# counter-defender-esp8266-pir-mk-1_0.net
KiCad netlist of a schematic drawn in EAGLE
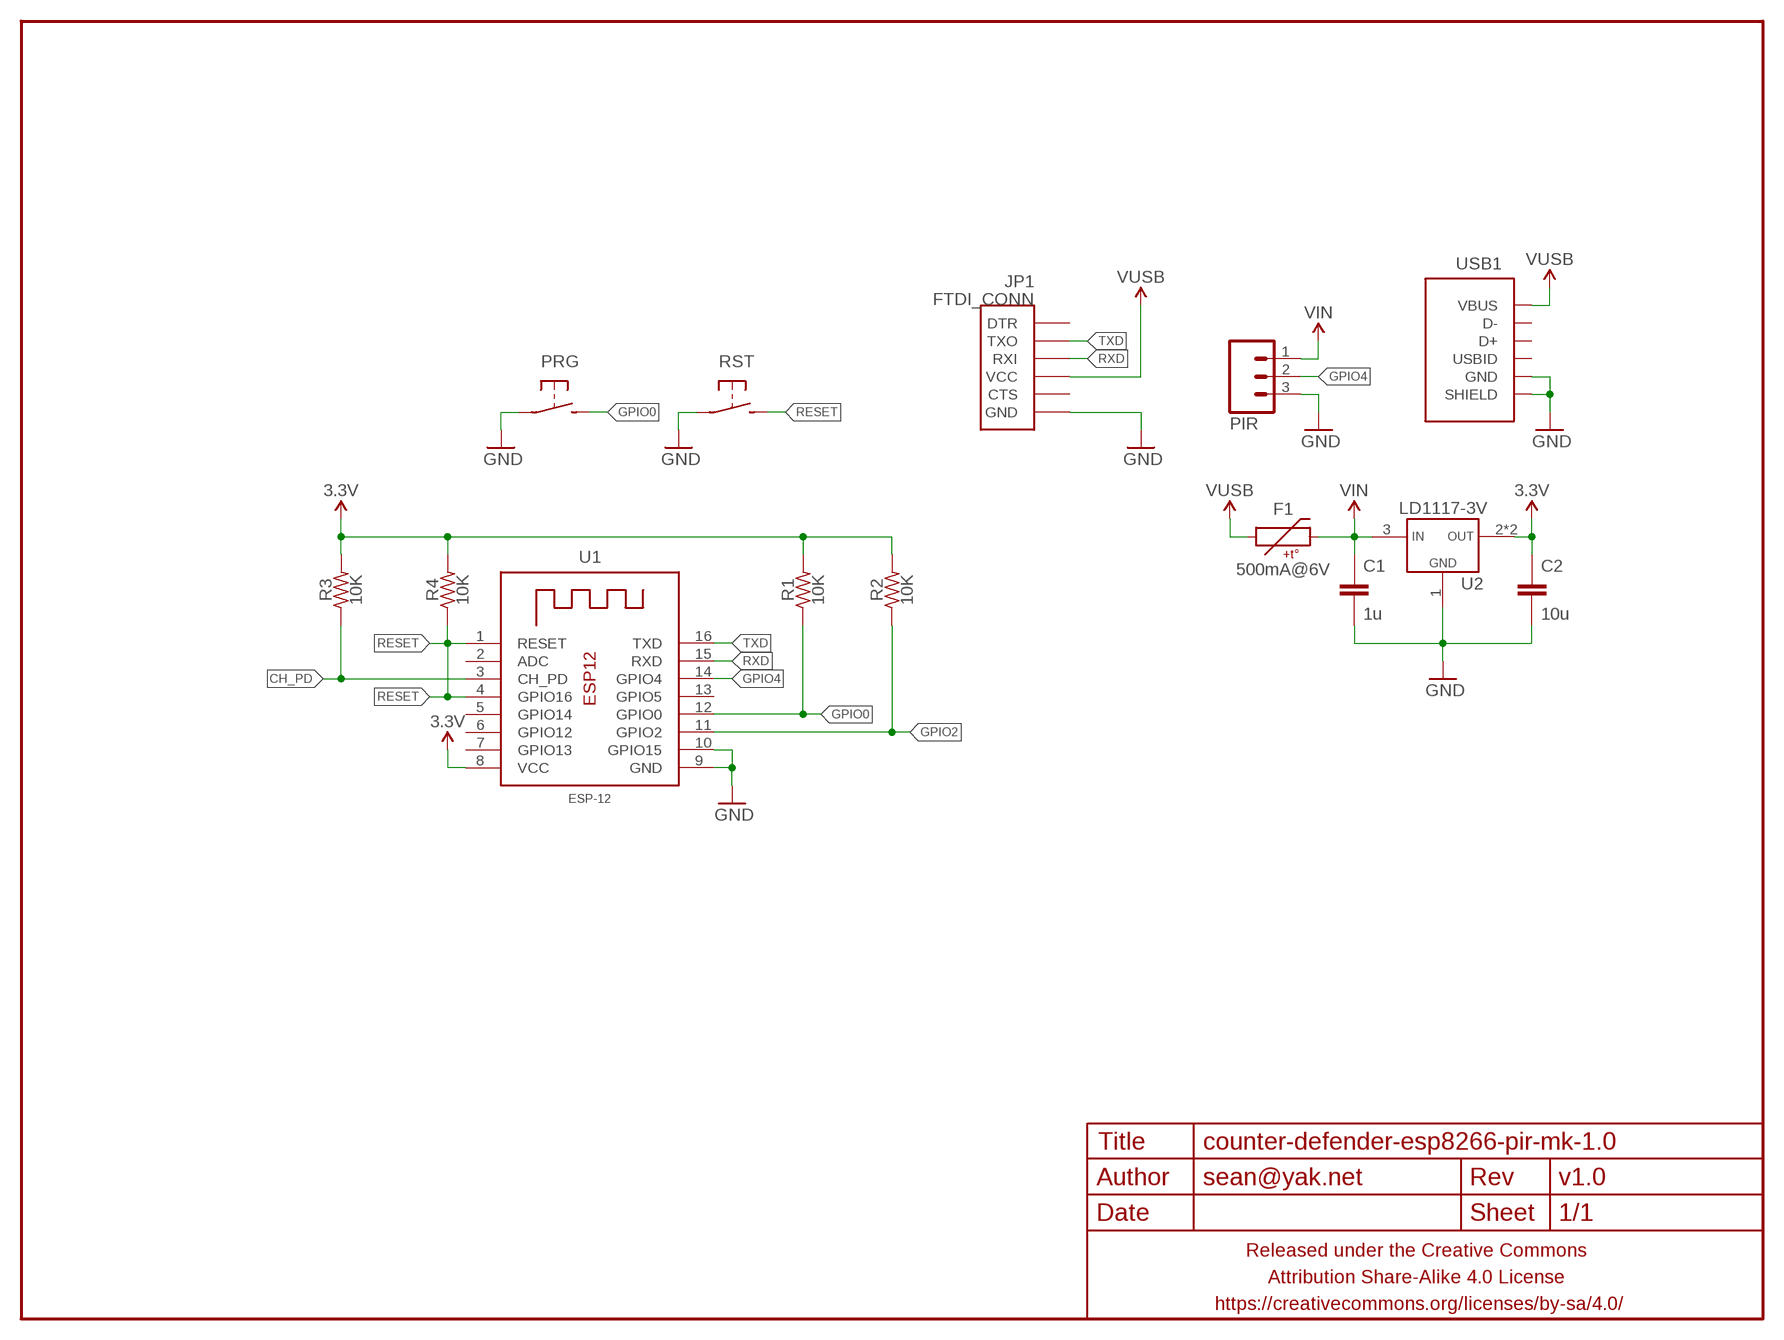
[diagram p0: schematic, sheet 1]

(export (version "E")
  (design (tool "Eeschema 10.0.6"))
  (components
    (comp (ref "C1")
      (value "1u")
      (footprint "eagle-import:C0805-TIGHTER")
      (libsource (lib "eagle-import") (part "CAPACITOR-CERAMICC0805-TIGHTER"))
    )
    (comp (ref "C2")
      (value "10u")
      (footprint "eagle-import:C0805-TIGHTER")
      (libsource (lib "eagle-import") (part "CAPACITOR-CERAMICC0805-TIGHTER"))
    )
    (comp (ref "F1")
      (value "500mA@6V")
      (footprint "eagle-import:PTC0805")
      (libsource (lib "eagle-import") (part "PTC0805"))
    )
    (comp (ref "FRAME1")
      (value "FRAME-LETTERNO_PACKAGE")
      (footprint "eagle-import:DUMMY")
      (fields (field (name "DESIGNER") "sean@yak.net") (field (name "VERSION") "v1.0"))
      (libsource (lib "eagle-import") (part "FRAME-LETTERNO_PACKAGE"))
    )
    (comp (ref "JP1")
      (value "FTDI_CONN")
      (footprint "eagle-import:FTDI_CONN")
      (libsource (lib "eagle-import") (part "FTDI_CONN"))
    )
    (comp (ref "PIR")
      (value "M03PTH-CENTERED")
      (footprint "eagle-import:1X03-CENTERED")
      (libsource (lib "eagle-import") (part "M03PTH-CENTERED"))
    )
    (comp (ref "PRG")
      (value "SPST-NO-TACTSMD-TINIER")
      (footprint "eagle-import:TACTILE_SWITCH_SMD_TINY")
      (libsource (lib "eagle-import") (part "SPST-NO-TACTSMD-TINIER"))
    )
    (comp (ref "R1")
      (value "10K")
      (footprint "eagle-import:R0603-TIGHTER")
      (libsource (lib "eagle-import") (part "RESISTORR0603-TIGHTER"))
    )
    (comp (ref "R2")
      (value "10K")
      (footprint "eagle-import:R0603-TIGHTER")
      (libsource (lib "eagle-import") (part "RESISTORR0603-TIGHTER"))
    )
    (comp (ref "R3")
      (value "10K")
      (footprint "eagle-import:R0603-TIGHTER")
      (libsource (lib "eagle-import") (part "RESISTORR0603-TIGHTER"))
    )
    (comp (ref "R4")
      (value "10K")
      (footprint "eagle-import:R0603-TIGHTER")
      (libsource (lib "eagle-import") (part "RESISTORR0603-TIGHTER"))
    )
    (comp (ref "RST")
      (value "SPST-NO-TACTSMD-TINIER")
      (footprint "eagle-import:TACTILE_SWITCH_SMD_TINY")
      (libsource (lib "eagle-import") (part "SPST-NO-TACTSMD-TINIER"))
    )
    (comp (ref "U1")
      (value "ESP-12")
      (footprint "eagle-import:ESP-12")
      (libsource (lib "eagle-import") (part "ESP-12"))
    )
    (comp (ref "U2")
      (value "LD1117-3V")
      (footprint "eagle-import:SOT223")
      (libsource (lib "eagle-import") (part "VREG_1117SOT223"))
    )
    (comp (ref "USB1")
      (value "USB-AB-SHIELDFCI-10103594-USB-MICRO-B-EVENLESS")
      (footprint "eagle-import:FCI-10103594-USB-MICRO-B-EVENLESS")
      (libsource (lib "eagle-import") (part "USB-AB-SHIELDFCI-10103594-USB-MICRO-B-EVENLESS"))
    )
  )
  (nets
    (net (code "1") (name "3.3V") (class "Default")
      (node (ref "C2") (pin "1") (pinfunction "1_1") (pintype "passive"))
      (node (ref "R1") (pin "2") (pinfunction "2_2") (pintype "passive"))
      (node (ref "R2") (pin "2") (pinfunction "2_2") (pintype "passive"))
      (node (ref "R3") (pin "2") (pinfunction "2_2") (pintype "passive"))
      (node (ref "R4") (pin "2") (pinfunction "2_2") (pintype "passive"))
      (node (ref "U1") (pin "8") (pinfunction "VCC_8") (pintype "power_in"))
      (node (ref "U2") (pin "2") (pinfunction "VOUT_2") (pintype "bidirectional"))
      (node (ref "U2") (pin "4") (pinfunction "VOUT_4") (pintype "bidirectional"))
    )
    (net (code "2") (name "CH_PD") (class "Default")
      (node (ref "R3") (pin "1") (pinfunction "1_1") (pintype "passive"))
      (node (ref "U1") (pin "3") (pinfunction "CH_PD_3") (pintype "input"))
    )
    (net (code "3") (name "GND") (class "Default")
      (node (ref "C1") (pin "2") (pinfunction "2_2") (pintype "passive"))
      (node (ref "C2") (pin "2") (pinfunction "2_2") (pintype "passive"))
      (node (ref "JP1") (pin "GND") (pinfunction "GND_GND") (pintype "bidirectional"))
      (node (ref "PIR") (pin "3") (pinfunction "3_3") (pintype "passive"))
      (node (ref "PRG") (pin "P$1") (pinfunction "1_P$1") (pintype "passive"))
      (node (ref "RST") (pin "P$1") (pinfunction "1_P$1") (pintype "passive"))
      (node (ref "U1") (pin "10") (pinfunction "GPIO15_10") (pintype "bidirectional"))
      (node (ref "U1") (pin "9") (pinfunction "GND_9") (pintype "power_in"))
      (node (ref "U2") (pin "1") (pinfunction "GND_1") (pintype "bidirectional"))
      (node (ref "USB1") (pin "5") (pinfunction "GND_5") (pintype "bidirectional"))
      (node (ref "USB1") (pin "SHIELD@1") (pinfunction "SHIELD_SHIELD@1") (pintype "bidirectional"))
      (node (ref "USB1") (pin "SHIELD@2") (pinfunction "SHIELD_SHIELD@2") (pintype "bidirectional"))
      (node (ref "USB1") (pin "SHIELD@3") (pinfunction "SHIELD_SHIELD@3") (pintype "bidirectional"))
      (node (ref "USB1") (pin "SHIELD@4") (pinfunction "SHIELD_SHIELD@4") (pintype "bidirectional"))
      (node (ref "USB1") (pin "SHIELD@5") (pinfunction "SHIELD_SHIELD@5") (pintype "bidirectional"))
      (node (ref "USB1") (pin "SHIELD@6") (pinfunction "SHIELD_SHIELD@6") (pintype "bidirectional"))
    )
    (net (code "4") (name "GPIO0") (class "Default")
      (node (ref "PRG") (pin "P$2") (pinfunction "2_P$2") (pintype "passive"))
      (node (ref "R1") (pin "1") (pinfunction "1_1") (pintype "passive"))
      (node (ref "U1") (pin "12") (pinfunction "GPIO0_12") (pintype "bidirectional"))
    )
    (net (code "5") (name "GPIO2") (class "Default")
      (node (ref "R2") (pin "1") (pinfunction "1_1") (pintype "passive"))
      (node (ref "U1") (pin "11") (pinfunction "GPIO2_11") (pintype "bidirectional"))
    )
    (net (code "6") (name "GPIO4") (class "Default")
      (node (ref "PIR") (pin "2") (pinfunction "2_2") (pintype "passive"))
      (node (ref "U1") (pin "14") (pinfunction "GPIO4_14") (pintype "bidirectional"))
    )
    (net (code "7") (name "RESET") (class "Default")
      (node (ref "R4") (pin "1") (pinfunction "1_1") (pintype "passive"))
      (node (ref "RST") (pin "P$2") (pinfunction "2_P$2") (pintype "passive"))
      (node (ref "U1") (pin "1") (pinfunction "RESET_1") (pintype "input"))
      (node (ref "U1") (pin "4") (pinfunction "GPIO16_4") (pintype "bidirectional"))
    )
    (net (code "8") (name "RXD") (class "Default")
      (node (ref "JP1") (pin "RXI") (pinfunction "RXI_RXI") (pintype "bidirectional"))
      (node (ref "U1") (pin "15") (pinfunction "RXD_15") (pintype "input"))
    )
    (net (code "9") (name "TXD") (class "Default")
      (node (ref "JP1") (pin "TXO") (pinfunction "TXO_TXO") (pintype "bidirectional"))
      (node (ref "U1") (pin "16") (pinfunction "TXD_16") (pintype "output"))
    )
    (net (code "10") (name "VIN") (class "Default")
      (node (ref "C1") (pin "1") (pinfunction "1_1") (pintype "passive"))
      (node (ref "F1") (pin "2") (pinfunction "2_2") (pintype "passive"))
      (node (ref "PIR") (pin "1") (pinfunction "1_1") (pintype "passive"))
      (node (ref "U2") (pin "3") (pinfunction "VIN_3") (pintype "bidirectional"))
    )
    (net (code "11") (name "VUSB") (class "Default")
      (node (ref "F1") (pin "1") (pinfunction "1_1") (pintype "passive"))
      (node (ref "JP1") (pin "VCC") (pinfunction "VCC_VCC") (pintype "bidirectional"))
      (node (ref "USB1") (pin "1") (pinfunction "VBUS_1") (pintype "bidirectional"))
    )
    (net (code "12") (name "unconnected-(JP1-PadCTS)") (class "Default")
      (node (ref "JP1") (pin "CTS") (pinfunction "CTS_CTS") (pintype "bidirectional"))
    )
    (net (code "13") (name "unconnected-(JP1-PadDTR)") (class "Default")
      (node (ref "JP1") (pin "DTR") (pinfunction "DTR_DTR") (pintype "bidirectional"))
    )
    (net (code "14") (name "unconnected-(U1-ADC-Pad2)") (class "Default")
      (node (ref "U1") (pin "2") (pinfunction "ADC_2") (pintype "passive"))
    )
    (net (code "15") (name "unconnected-(U1-GPIO5-Pad13)") (class "Default")
      (node (ref "U1") (pin "13") (pinfunction "GPIO5_13") (pintype "bidirectional"))
    )
    (net (code "16") (name "unconnected-(U1-GPIO12-Pad6)") (class "Default")
      (node (ref "U1") (pin "6") (pinfunction "GPIO12_6") (pintype "bidirectional"))
    )
    (net (code "17") (name "unconnected-(U1-GPIO13-Pad7)") (class "Default")
      (node (ref "U1") (pin "7") (pinfunction "GPIO13_7") (pintype "bidirectional"))
    )
    (net (code "18") (name "unconnected-(U1-GPIO14-Pad5)") (class "Default")
      (node (ref "U1") (pin "5") (pinfunction "GPIO14_5") (pintype "bidirectional"))
    )
    (net (code "19") (name "unconnected-(USB1-D+-Pad3)") (class "Default")
      (node (ref "USB1") (pin "3") (pinfunction "D+_3") (pintype "bidirectional"))
    )
    (net (code "20") (name "unconnected-(USB1-D--Pad2)") (class "Default")
      (node (ref "USB1") (pin "2") (pinfunction "D-_2") (pintype "bidirectional"))
    )
    (net (code "21") (name "unconnected-(USB1-USBID-Pad4)") (class "Default")
      (node (ref "USB1") (pin "4") (pinfunction "USBID_4") (pintype "bidirectional"))
    )
  )
)
